# Microcontroller.net
KiCad netlist of a schematic drawn in Altium Designer
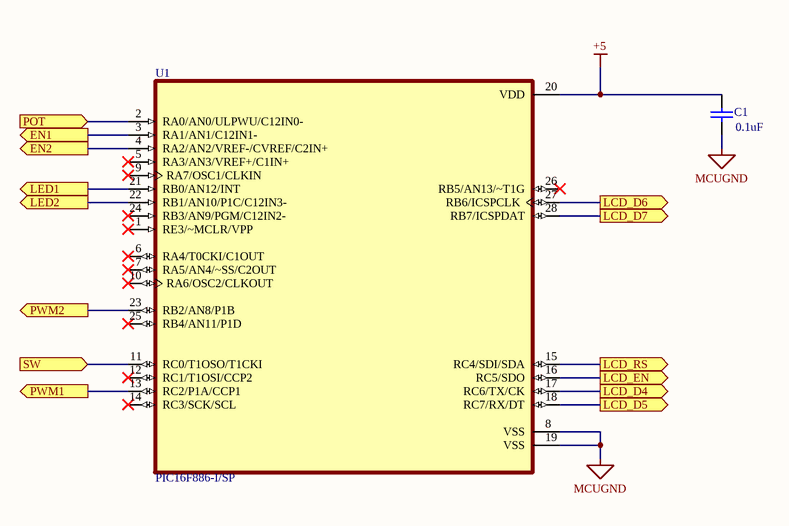
[diagram p0: Microcontroller.SchDoc]

(export (version "E")
  (design (tool "Eeschema 10.0.6"))
  (components
    (comp (ref "C1")
      (value "0.1uF")
      (footprint "RAD-0.3")
      (description "Capacitor")
      (fields (field (name "Comment") "Cap") (field (name "PUBLISHER") "Altium Limited"))
      (libsource (lib "Miscellaneous Devices") (part "Cap"))
    )
    (comp (ref "U1")
      (value "PIC16F886-I/SP")
      (footprint "DIP762W46P254L3467H457Q28")
      (description "PIC PICÂ® 16F Microcontroller IC 8-Bit 20MHz 14KB _8K x 14_ FLASH 28-SPDIP")
      (fields (field (name "MF") "Microchip"))
      (libsource (lib "PIC16F886-I_SP") (part "PIC16F886-I/SP"))
    )
  )
  (nets
    (net (code "1") (name "+5") (class "Default")
      (node (ref "C1") (pin "2") (pinfunction "2_2") (pintype "passive"))
      (node (ref "U1") (pin "20") (pinfunction "VDD_20") (pintype "power_in"))
    )
    (net (code "2") (name "/EN1") (class "Default")
      (node (ref "U1") (pin "3") (pinfunction "RA1/AN1/C12IN1-_3") (pintype "input"))
    )
    (net (code "3") (name "/EN2") (class "Default")
      (node (ref "U1") (pin "4") (pinfunction "RA2/AN2/VREF-/CVREF/C2IN+_4") (pintype "input"))
    )
    (net (code "4") (name "/LCD_D4") (class "Default")
      (node (ref "U1") (pin "17") (pinfunction "RC6/TX/CK_17") (pintype "bidirectional"))
    )
    (net (code "5") (name "/LCD_D5") (class "Default")
      (node (ref "U1") (pin "18") (pinfunction "RC7/RX/DT_18") (pintype "bidirectional"))
    )
    (net (code "6") (name "/LCD_D6") (class "Default")
      (node (ref "U1") (pin "27") (pinfunction "RB6/ICSPCLK_27") (pintype "bidirectional"))
    )
    (net (code "7") (name "/LCD_D7") (class "Default")
      (node (ref "U1") (pin "28") (pinfunction "RB7/ICSPDAT_28") (pintype "bidirectional"))
    )
    (net (code "8") (name "/LCD_EN") (class "Default")
      (node (ref "U1") (pin "16") (pinfunction "RC5/SDO_16") (pintype "bidirectional"))
    )
    (net (code "9") (name "/LCD_RS") (class "Default")
      (node (ref "U1") (pin "15") (pinfunction "RC4/SDI/SDA_15") (pintype "bidirectional"))
    )
    (net (code "10") (name "/LED1") (class "Default")
      (node (ref "U1") (pin "21") (pinfunction "RB0/AN12/INT_21") (pintype "input"))
    )
    (net (code "11") (name "/LED2") (class "Default")
      (node (ref "U1") (pin "22") (pinfunction "RB1/AN10/P1C/C12IN3-_22") (pintype "input"))
    )
    (net (code "12") (name "/POT") (class "Default")
      (node (ref "U1") (pin "2") (pinfunction "RA0/AN0/ULPWU/C12IN0-_2") (pintype "input"))
    )
    (net (code "13") (name "/PWM1") (class "Default")
      (node (ref "U1") (pin "13") (pinfunction "RC2/P1A/CCP1_13") (pintype "bidirectional"))
    )
    (net (code "14") (name "/PWM2") (class "Default")
      (node (ref "U1") (pin "23") (pinfunction "RB2/AN8/P1B_23") (pintype "bidirectional"))
    )
    (net (code "15") (name "/SW") (class "Default")
      (node (ref "U1") (pin "11") (pinfunction "RC0/T1OSO/T1CKI_11") (pintype "bidirectional"))
    )
    (net (code "16") (name "MCUGND") (class "Default")
      (node (ref "C1") (pin "1") (pinfunction "1_1") (pintype "passive"))
      (node (ref "U1") (pin "19") (pinfunction "VSS_19") (pintype "power_in"))
      (node (ref "U1") (pin "8") (pinfunction "VSS_8") (pintype "power_in"))
    )
    (net (code "17") (name "unconnected-(U1-RA3{slash}AN3{slash}VREF+{slash}C1IN+-Pad5)") (class "Default")
      (node (ref "U1") (pin "5") (pinfunction "RA3/AN3/VREF+/C1IN+_5") (pintype "input+no_connect"))
    )
    (net (code "18") (name "unconnected-(U1-RA4{slash}T0CKI{slash}C1OUT-Pad6)") (class "Default")
      (node (ref "U1") (pin "6") (pinfunction "RA4/T0CKI/C1OUT_6") (pintype "bidirectional+no_connect"))
    )
    (net (code "19") (name "unconnected-(U1-RA5{slash}AN4{slash}~SS{slash}C2OUT-Pad7)") (class "Default")
      (node (ref "U1") (pin "7") (pinfunction "RA5/AN4/~SS/C2OUT_7") (pintype "bidirectional+no_connect"))
    )
    (net (code "20") (name "unconnected-(U1-RA6{slash}OSC2{slash}CLKOUT-Pad10)") (class "Default")
      (node (ref "U1") (pin "10") (pinfunction "RA6/OSC2/CLKOUT_10") (pintype "bidirectional+no_connect"))
    )
    (net (code "21") (name "unconnected-(U1-RA7{slash}OSC1{slash}CLKIN-Pad9)") (class "Default")
      (node (ref "U1") (pin "9") (pinfunction "RA7/OSC1/CLKIN_9") (pintype "input+no_connect"))
    )
    (net (code "22") (name "unconnected-(U1-RB3{slash}AN9{slash}PGM{slash}C12IN2--Pad24)") (class "Default")
      (node (ref "U1") (pin "24") (pinfunction "RB3/AN9/PGM/C12IN2-_24") (pintype "input+no_connect"))
    )
    (net (code "23") (name "unconnected-(U1-RB4{slash}AN11{slash}P1D-Pad25)") (class "Default")
      (node (ref "U1") (pin "25") (pinfunction "RB4/AN11/P1D_25") (pintype "bidirectional+no_connect"))
    )
    (net (code "24") (name "unconnected-(U1-RB5{slash}AN13{slash}~T1G-Pad26)") (class "Default")
      (node (ref "U1") (pin "26") (pinfunction "RB5/AN13/~T1G_26") (pintype "bidirectional+no_connect"))
    )
    (net (code "25") (name "unconnected-(U1-RC1{slash}T1OSI{slash}CCP2-Pad12)") (class "Default")
      (node (ref "U1") (pin "12") (pinfunction "RC1/T1OSI/CCP2_12") (pintype "bidirectional+no_connect"))
    )
    (net (code "26") (name "unconnected-(U1-RC3{slash}SCK{slash}SCL-Pad14)") (class "Default")
      (node (ref "U1") (pin "14") (pinfunction "RC3/SCK/SCL_14") (pintype "bidirectional+no_connect"))
    )
    (net (code "27") (name "unconnected-(U1-RE3{slash}~MCLR{slash}VPP-Pad1)") (class "Default")
      (node (ref "U1") (pin "1") (pinfunction "RE3/~MCLR/VPP_1") (pintype "input+no_connect"))
    )
  )
)
